# PG05_Schematic_Sheet3.net
KiCad netlist of a schematic drawn in Altium Designer
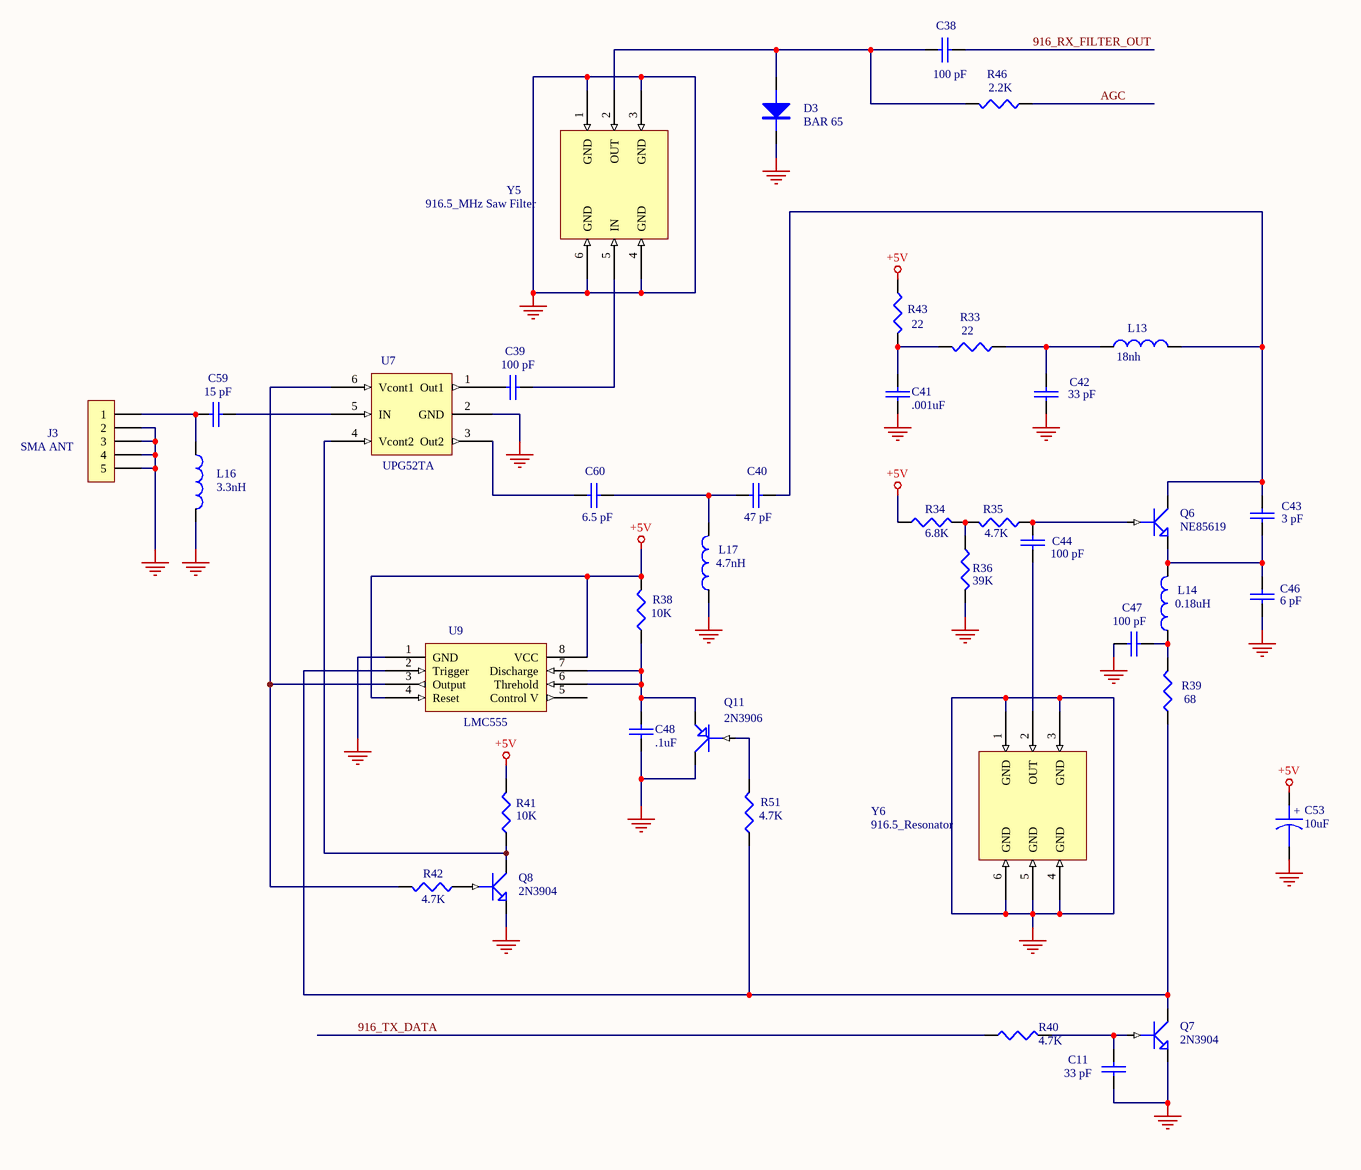
[diagram p0: PG05_Schematic Sheet3.SchDoc]

(export (version "E")
  (design (tool "Eeschema 10.0.6"))
  (components
    (comp (ref "C11")
      (value "33 pF")
      (footprint "0603")
      (description "Capacitor")
      (libsource (lib "*") (part "CAP"))
    )
    (comp (ref "C38")
      (value "100 pF")
      (footprint "0603")
      (description "Capacitor")
      (libsource (lib "*") (part "CAP"))
    )
    (comp (ref "C39")
      (value "100 pF")
      (footprint "0603")
      (description "Capacitor")
      (libsource (lib "*") (part "CAP"))
    )
    (comp (ref "C40")
      (value "47 pF")
      (footprint "0603")
      (description "Capacitor")
      (libsource (lib "*") (part "CAP"))
    )
    (comp (ref "C41")
      (value ".001uF")
      (footprint "0603")
      (description "Capacitor")
      (libsource (lib "*") (part "CAP"))
    )
    (comp (ref "C42")
      (value "33 pF")
      (footprint "0603")
      (description "Capacitor")
      (libsource (lib "*") (part "CAP"))
    )
    (comp (ref "C43")
      (value "3 pF")
      (footprint "0603")
      (description "Capacitor")
      (libsource (lib "*") (part "CAP"))
    )
    (comp (ref "C44")
      (value "100 pF")
      (footprint "0603")
      (description "Capacitor")
      (libsource (lib "*") (part "CAP"))
    )
    (comp (ref "C46")
      (value "6 pF")
      (footprint "0603")
      (description "Capacitor")
      (libsource (lib "*") (part "CAP"))
    )
    (comp (ref "C47")
      (value "100 pF")
      (footprint "0603")
      (description "Capacitor")
      (libsource (lib "*") (part "CAP"))
    )
    (comp (ref "C48")
      (value ".1uF")
      (footprint "0603")
      (description "Capacitor")
      (libsource (lib "*") (part "CAP"))
    )
    (comp (ref "C53")
      (value "10uF")
      (footprint "CAP A CASE")
      (description "Capacitor")
      (libsource (lib "*") (part "CAPACITOR POL"))
    )
    (comp (ref "C59")
      (value "15 pF")
      (footprint "0603")
      (description "Capacitor")
      (libsource (lib "*") (part "CAP"))
    )
    (comp (ref "C60")
      (value "6.5 pF")
      (footprint "0603")
      (description "Capacitor")
      (libsource (lib "*") (part "CAP"))
    )
    (comp (ref "D3")
      (value "BAR 65")
      (footprint "DIODE SC79")
      (description "Diode")
      (libsource (lib "*") (part "DIODE"))
    )
    (comp (ref "J3")
      (value "SMA ANT")
      (footprint "50 OHM ANT")
      (description "Connector")
      (libsource (lib "*") (part "CON5"))
    )
    (comp (ref "L13")
      (value "18nh")
      (footprint "0603")
      (description "INDUCTOR 18NH 5% 0603 SMD")
      (fields (field (name "VENDORPARTNUMBER") "PCD1976TR-ND") (field (name "MFG") "Panasdonic"))
      (libsource (lib "*") (part "INDUCTOR"))
    )
    (comp (ref "L14") (value "0.18uH") (footprint "0603") (libsource (lib "*") (part "INDUCTOR")))
    (comp (ref "L16") (value "3.3nH") (footprint "0603") (libsource (lib "*") (part "INDUCTOR")))
    (comp (ref "L17") (value "4.7nH") (footprint "0603") (libsource (lib "*") (part "INDUCTOR")))
    (comp (ref "Q6")
      (value "NE85619")
      (footprint "3 PIN ULTRA SUPER MINI MOLD")
      (description "NPN Transistor")
      (libsource (lib "*") (part "NPN1"))
    )
    (comp (ref "Q7")
      (value "2N3904")
      (footprint "SOT23 TRANS")
      (description "NPN Transistor")
      (libsource (lib "*") (part "NPN1"))
    )
    (comp (ref "Q8")
      (value "2N3904")
      (footprint "SOT23 TRANS")
      (description "NPN Transistor")
      (libsource (lib "*") (part "NPN1"))
    )
    (comp (ref "Q11")
      (value "2N3906")
      (footprint "SOT23 TRANS")
      (description "PNP Transistor")
      (libsource (lib "*") (part "PNP1"))
    )
    (comp (ref "R33") (value "22") (footprint "0603") (libsource (lib "*") (part "RESISTOR")))
    (comp (ref "R34") (value "6.8K") (footprint "0603") (libsource (lib "*") (part "RESISTOR")))
    (comp (ref "R35") (value "4.7K") (footprint "0603") (libsource (lib "*") (part "RESISTOR")))
    (comp (ref "R36") (value "39K") (footprint "0603") (libsource (lib "*") (part "RESISTOR")))
    (comp (ref "R38") (value "10K") (footprint "0603") (libsource (lib "*") (part "RESISTOR")))
    (comp (ref "R39") (value "68") (footprint "0603") (libsource (lib "*") (part "RESISTOR")))
    (comp (ref "R40") (value "4.7K") (footprint "0603") (libsource (lib "*") (part "RESISTOR")))
    (comp (ref "R41") (value "10K") (footprint "0603") (libsource (lib "*") (part "RESISTOR")))
    (comp (ref "R42") (value "4.7K") (footprint "0603") (libsource (lib "*") (part "RESISTOR")))
    (comp (ref "R43") (value "22") (footprint "0603") (libsource (lib "*") (part "RESISTOR")))
    (comp (ref "R46") (value "2.2K") (footprint "0603") (libsource (lib "*") (part "RESISTOR")))
    (comp (ref "R51") (value "4.7K") (footprint "0603") (libsource (lib "*") (part "RESISTOR")))
    (comp (ref "U7") (value "UPG52TA") (footprint "TO6") (libsource (lib "*") (part "UPG152TA_0")))
    (comp (ref "U9") (value "LMC555") (footprint "SO8 SMALL") (libsource (lib "*") (part "LMC555")))
    (comp (ref "Y5")
      (value "916.5_MHz Saw Filter")
      (footprint "RESONATOR2")
      (libsource (lib "*") (part "RESONATOR3"))
    )
    (comp (ref "Y6")
      (value "916.5_Resonator")
      (footprint "RESONATOR2")
      (libsource (lib "*") (part "RESONATOR2"))
    )
  )
  (nets
    (net (code "1") (name "+5V") (class "Default")
      (node (ref "C53") (pin "1") (pinfunction "1_1") (pintype "passive"))
      (node (ref "R34") (pin "1") (pinfunction "1_1") (pintype "passive"))
      (node (ref "R38") (pin "2") (pinfunction "2_2") (pintype "passive"))
      (node (ref "R41") (pin "2") (pinfunction "2_2") (pintype "passive"))
      (node (ref "R43") (pin "1") (pinfunction "1_1") (pintype "passive"))
      (node (ref "U9") (pin "4") (pinfunction "Reset_4") (pintype "input"))
      (node (ref "U9") (pin "8") (pinfunction "VCC_8") (pintype "power_in"))
    )
    (net (code "2") (name "/916_RX_FILTER_OUT") (class "Default")
      (node (ref "C38") (pin "2") (pinfunction "2_2") (pintype "passive"))
    )
    (net (code "3") (name "/916_TX_DATA") (class "Default")
      (node (ref "R40") (pin "1") (pinfunction "1_1") (pintype "passive"))
    )
    (net (code "4") (name "/AGC") (class "Default")
      (node (ref "R46") (pin "1") (pinfunction "1_1") (pintype "passive"))
    )
    (net (code "5") (name "GND_SIGNAL") (class "Default")
      (node (ref "C11") (pin "2") (pinfunction "2_2") (pintype "passive"))
      (node (ref "C41") (pin "2") (pinfunction "2_2") (pintype "passive"))
      (node (ref "C42") (pin "2") (pinfunction "2_2") (pintype "passive"))
      (node (ref "C46") (pin "2") (pinfunction "2_2") (pintype "passive"))
      (node (ref "C47") (pin "1") (pinfunction "1_1") (pintype "passive"))
      (node (ref "C48") (pin "2") (pinfunction "2_2") (pintype "passive"))
      (node (ref "C53") (pin "2") (pinfunction "2_2") (pintype "passive"))
      (node (ref "D3") (pin "K") (pinfunction "K_K") (pintype "passive"))
      (node (ref "J3") (pin "2") (pinfunction "2_2") (pintype "passive"))
      (node (ref "J3") (pin "3") (pinfunction "3_3") (pintype "passive"))
      (node (ref "J3") (pin "4") (pinfunction "4_4") (pintype "passive"))
      (node (ref "J3") (pin "5") (pinfunction "5_5") (pintype "passive"))
      (node (ref "L16") (pin "2") (pinfunction "2_2") (pintype "passive"))
      (node (ref "L17") (pin "1") (pinfunction "1_1") (pintype "passive"))
      (node (ref "Q11") (pin "C") (pinfunction "C_C") (pintype "passive"))
      (node (ref "Q7") (pin "E") (pinfunction "E_E") (pintype "passive"))
      (node (ref "Q8") (pin "E") (pinfunction "E_E") (pintype "passive"))
      (node (ref "R36") (pin "2") (pinfunction "2_2") (pintype "passive"))
      (node (ref "U7") (pin "2") (pinfunction "GND_2") (pintype "power_in"))
      (node (ref "U9") (pin "1") (pinfunction "GND_1") (pintype "power_in"))
      (node (ref "Y5") (pin "1") (pinfunction "GND_1") (pintype "input"))
      (node (ref "Y5") (pin "3") (pinfunction "GND_3") (pintype "input"))
      (node (ref "Y5") (pin "4") (pinfunction "GND_4") (pintype "input"))
      (node (ref "Y5") (pin "6") (pinfunction "GND_6") (pintype "input"))
      (node (ref "Y6") (pin "1") (pinfunction "GND_1") (pintype "input"))
      (node (ref "Y6") (pin "3") (pinfunction "GND_3") (pintype "input"))
      (node (ref "Y6") (pin "4") (pinfunction "GND_4") (pintype "input"))
      (node (ref "Y6") (pin "5") (pinfunction "GND_5") (pintype "input"))
      (node (ref "Y6") (pin "6") (pinfunction "GND_6") (pintype "input"))
    )
    (net (code "6") (name "Net-(C11-Pad1)") (class "Default")
      (node (ref "C11") (pin "1") (pinfunction "1_1") (pintype "passive"))
      (node (ref "Q7") (pin "B") (pinfunction "B_B") (pintype "input"))
      (node (ref "R40") (pin "2") (pinfunction "2_2") (pintype "passive"))
    )
    (net (code "7") (name "Net-(C40-Pad1)") (class "Default")
      (node (ref "C40") (pin "1") (pinfunction "1_1") (pintype "passive"))
      (node (ref "C60") (pin "2") (pinfunction "2_2") (pintype "passive"))
      (node (ref "L17") (pin "2") (pinfunction "2_2") (pintype "passive"))
    )
    (net (code "8") (name "Net-(C40-Pad2)") (class "Default")
      (node (ref "C40") (pin "2") (pinfunction "2_2") (pintype "passive"))
      (node (ref "C43") (pin "1") (pinfunction "1_1") (pintype "passive"))
      (node (ref "L13") (pin "2") (pinfunction "2_2") (pintype "passive"))
      (node (ref "Q6") (pin "C") (pinfunction "C_C") (pintype "passive"))
    )
    (net (code "9") (name "Net-(C41-Pad1)") (class "Default")
      (node (ref "C41") (pin "1") (pinfunction "1_1") (pintype "passive"))
      (node (ref "R33") (pin "2") (pinfunction "2_2") (pintype "passive"))
      (node (ref "R43") (pin "2") (pinfunction "2_2") (pintype "passive"))
    )
    (net (code "10") (name "Net-(C42-Pad1)") (class "Default")
      (node (ref "C42") (pin "1") (pinfunction "1_1") (pintype "passive"))
      (node (ref "L13") (pin "1") (pinfunction "1_1") (pintype "passive"))
      (node (ref "R33") (pin "1") (pinfunction "1_1") (pintype "passive"))
    )
    (net (code "11") (name "Net-(C43-Pad2)") (class "Default")
      (node (ref "C43") (pin "2") (pinfunction "2_2") (pintype "passive"))
      (node (ref "C46") (pin "1") (pinfunction "1_1") (pintype "passive"))
      (node (ref "L14") (pin "2") (pinfunction "2_2") (pintype "passive"))
      (node (ref "Q6") (pin "E") (pinfunction "E_E") (pintype "passive"))
    )
    (net (code "12") (name "Net-(C44-Pad1)") (class "Default")
      (node (ref "C44") (pin "1") (pinfunction "1_1") (pintype "passive"))
      (node (ref "Q6") (pin "B") (pinfunction "B_B") (pintype "input"))
      (node (ref "R35") (pin "1") (pinfunction "1_1") (pintype "passive"))
    )
    (net (code "13") (name "Net-(C47-Pad2)") (class "Default")
      (node (ref "C47") (pin "2") (pinfunction "2_2") (pintype "passive"))
      (node (ref "L14") (pin "1") (pinfunction "1_1") (pintype "passive"))
      (node (ref "R39") (pin "2") (pinfunction "2_2") (pintype "passive"))
    )
    (net (code "14") (name "Net-(C59-Pad1)") (class "Default")
      (node (ref "C59") (pin "1") (pinfunction "1_1") (pintype "passive"))
      (node (ref "J3") (pin "1") (pinfunction "1_1") (pintype "passive"))
      (node (ref "L16") (pin "1") (pinfunction "1_1") (pintype "passive"))
    )
    (net (code "15") (name "Net-(Q8-PadB)") (class "Default")
      (node (ref "Q8") (pin "B") (pinfunction "B_B") (pintype "input"))
      (node (ref "R42") (pin "1") (pinfunction "1_1") (pintype "passive"))
    )
    (net (code "16") (name "Net-(Q11-PadB)") (class "Default")
      (node (ref "Q11") (pin "B") (pinfunction "B_B") (pintype "input"))
      (node (ref "R51") (pin "2") (pinfunction "2_2") (pintype "passive"))
    )
    (net (code "17") (name "Net-(R34-Pad2)") (class "Default")
      (node (ref "R34") (pin "2") (pinfunction "2_2") (pintype "passive"))
      (node (ref "R35") (pin "2") (pinfunction "2_2") (pintype "passive"))
      (node (ref "R36") (pin "1") (pinfunction "1_1") (pintype "passive"))
    )
    (net (code "18") (name "Net-(U7-IN)") (class "Default")
      (node (ref "C59") (pin "2") (pinfunction "2_2") (pintype "passive"))
      (node (ref "U7") (pin "5") (pinfunction "IN_5") (pintype "input"))
    )
    (net (code "19") (name "Net-(U7-Out1)") (class "Default")
      (node (ref "C39") (pin "1") (pinfunction "1_1") (pintype "passive"))
      (node (ref "U7") (pin "1") (pinfunction "Out1_1") (pintype "output"))
    )
    (net (code "20") (name "Net-(U7-Out2)") (class "Default")
      (node (ref "C60") (pin "1") (pinfunction "1_1") (pintype "passive"))
      (node (ref "U7") (pin "3") (pinfunction "Out2_3") (pintype "output"))
    )
    (net (code "21") (name "Net-(U7-Vcont1)") (class "Default")
      (node (ref "R42") (pin "2") (pinfunction "2_2") (pintype "passive"))
      (node (ref "U7") (pin "6") (pinfunction "Vcont1_6") (pintype "input"))
      (node (ref "U9") (pin "3") (pinfunction "Output_3") (pintype "output"))
    )
    (net (code "22") (name "Net-(U7-Vcont2)") (class "Default")
      (node (ref "Q8") (pin "C") (pinfunction "C_C") (pintype "passive"))
      (node (ref "R41") (pin "1") (pinfunction "1_1") (pintype "passive"))
      (node (ref "U7") (pin "4") (pinfunction "Vcont2_4") (pintype "input"))
    )
    (net (code "23") (name "Net-(U9-Discharge)") (class "Default")
      (node (ref "C48") (pin "1") (pinfunction "1_1") (pintype "passive"))
      (node (ref "Q11") (pin "E") (pinfunction "E_E") (pintype "passive"))
      (node (ref "R38") (pin "1") (pinfunction "1_1") (pintype "passive"))
      (node (ref "U9") (pin "6") (pinfunction "Threhold_6") (pintype "input"))
      (node (ref "U9") (pin "7") (pinfunction "Discharge_7") (pintype "input"))
    )
    (net (code "24") (name "Net-(U9-Trigger)") (class "Default")
      (node (ref "Q7") (pin "C") (pinfunction "C_C") (pintype "passive"))
      (node (ref "R39") (pin "1") (pinfunction "1_1") (pintype "passive"))
      (node (ref "R51") (pin "1") (pinfunction "1_1") (pintype "passive"))
      (node (ref "U9") (pin "2") (pinfunction "Trigger_2") (pintype "input"))
    )
    (net (code "25") (name "Net-(Y5-IN)") (class "Default")
      (node (ref "C39") (pin "2") (pinfunction "2_2") (pintype "passive"))
      (node (ref "Y5") (pin "5") (pinfunction "IN_5") (pintype "input"))
    )
    (net (code "26") (name "Net-(Y5-OUT)") (class "Default")
      (node (ref "C38") (pin "1") (pinfunction "1_1") (pintype "passive"))
      (node (ref "D3") (pin "A") (pinfunction "A_A") (pintype "passive"))
      (node (ref "R46") (pin "2") (pinfunction "2_2") (pintype "passive"))
      (node (ref "Y5") (pin "2") (pinfunction "OUT_2") (pintype "input"))
    )
    (net (code "27") (name "Net-(Y6-OUT)") (class "Default")
      (node (ref "C44") (pin "2") (pinfunction "2_2") (pintype "passive"))
      (node (ref "Y6") (pin "2") (pinfunction "OUT_2") (pintype "input"))
    )
    (net (code "28") (name "unconnected-(U9-Control_V-Pad5)") (class "Default")
      (node (ref "U9") (pin "5") (pinfunction "Control_V_5") (pintype "output"))
    )
  )
)
